# shoot1.net
KiCad netlist of a schematic drawn in Altium Designer
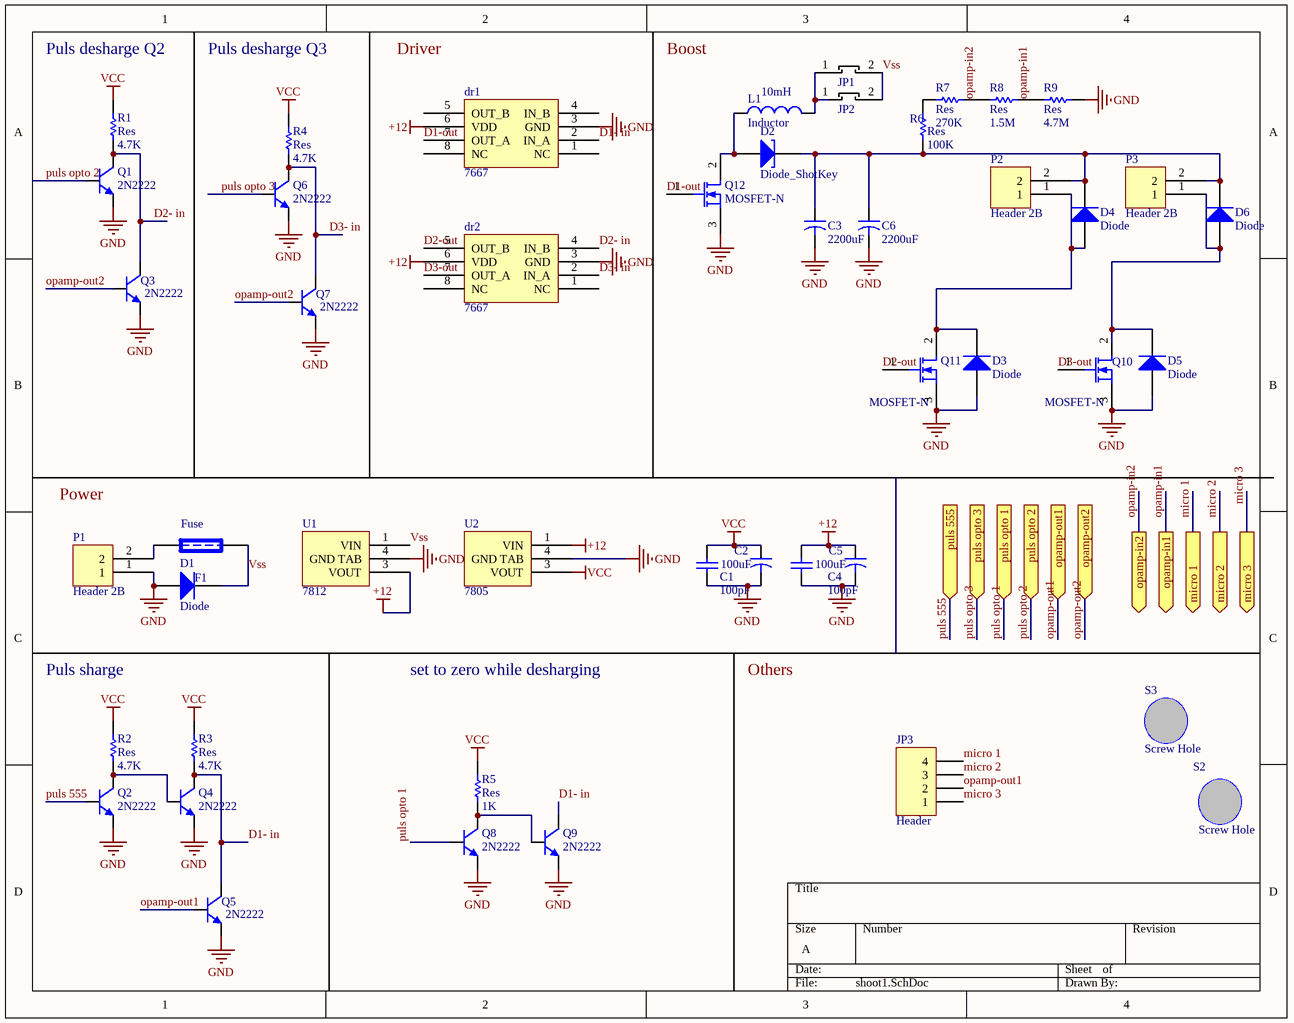
[diagram p0: shoot1.SchDoc]

(export (version "E")
  (design (tool "Eeschema 10.0.6"))
  (components
    (comp (ref "C1")
      (value "100pF")
      (footprint "2012[0805]")
      (description "Capacitor")
      (fields (field (name "Comment") "Cap_UP") (field (name "PUBLISHER") "Altium Limited"))
      (libsource (lib "KN2CLib") (part "Cap_UP"))
    )
    (comp (ref "C2")
      (value "100uF")
      (footprint "EL_M")
      (description "Capacitor")
      (fields (field (name "Comment") "Cap_El") (field (name "PUBLISHER") "Altium Limited"))
      (libsource (lib "KN2CLib") (part "Cap_El"))
    )
    (comp (ref "C3")
      (value "2200uF")
      (footprint "CAP")
      (description "Capacitor")
      (fields (field (name "Comment") "Cap_El_200V") (field (name "PUBLISHER") "Altium Limited"))
      (libsource (lib "KN2CLib") (part "Cap_El_200V"))
    )
    (comp (ref "C4")
      (value "100pF")
      (footprint "2012[0805]")
      (description "Capacitor")
      (fields (field (name "Comment") "Cap_UP") (field (name "PUBLISHER") "Altium Limited"))
      (libsource (lib "KN2CLib") (part "Cap_UP"))
    )
    (comp (ref "C5")
      (value "100uF")
      (footprint "EL_M")
      (description "Capacitor")
      (fields (field (name "Comment") "Cap_El") (field (name "PUBLISHER") "Altium Limited"))
      (libsource (lib "KN2CLib") (part "Cap_El"))
    )
    (comp (ref "C6")
      (value "2200uF")
      (footprint "CAP")
      (description "Capacitor")
      (fields (field (name "Comment") "Cap_El_200V") (field (name "PUBLISHER") "Altium Limited"))
      (libsource (lib "KN2CLib") (part "Cap_El_200V"))
    )
    (comp (ref "D1")
      (value "Diode")
      (footprint "US1M")
      (description "1 Amp General Purpose Rectifier")
      (fields (field (name "PUBLISHER") "Altium Limited"))
      (libsource (lib "KN2CLib") (part "Diode"))
    )
    (comp (ref "D2")
      (value "Diode_ShotKey")
      (footprint "TO-220A - duplicate")
      (description "1 Amp General Purpose Rectifier")
      (fields (field (name "PUBLISHER") "Altium Limited"))
      (libsource (lib "KN2CLib") (part "Diode_ShotKey"))
    )
    (comp (ref "D3")
      (value "Diode")
      (footprint "DIO10.46-5.3X2.8")
      (description "1 Amp General Purpose Rectifier")
      (fields (field (name "PUBLISHER") "Altium Limited"))
      (libsource (lib "KN2CLib") (part "Diode"))
    )
    (comp (ref "D4")
      (value "Diode")
      (footprint "DIO10.46-5.3X2.8")
      (description "1 Amp General Purpose Rectifier")
      (fields (field (name "PUBLISHER") "Altium Limited"))
      (libsource (lib "KN2CLib") (part "Diode"))
    )
    (comp (ref "D5")
      (value "Diode")
      (footprint "DIO10.46-5.3X2.8")
      (description "1 Amp General Purpose Rectifier")
      (fields (field (name "PUBLISHER") "Altium Limited"))
      (libsource (lib "KN2CLib") (part "Diode"))
    )
    (comp (ref "D6")
      (value "Diode")
      (footprint "DIO10.46-5.3X2.8")
      (description "1 Amp General Purpose Rectifier")
      (fields (field (name "PUBLISHER") "Altium Limited"))
      (libsource (lib "KN2CLib") (part "Diode"))
    )
    (comp (ref "dr1")
      (value "7667")
      (footprint "8 pin SOIC_M")
      (description "Dual MOSFET Driver")
      (libsource (lib "KN2CLib") (part "7667"))
    )
    (comp (ref "dr2")
      (value "7667")
      (footprint "8 pin SOIC_M")
      (description "Dual MOSFET Driver")
      (libsource (lib "KN2CLib") (part "7667"))
    )
    (comp (ref "F1")
      (value "Fuse")
      (footprint "fuse new")
      (fields (field (name "PUBLISHER") "Altium Limited"))
      (libsource (lib "KN2CLib") (part "Fuse"))
    )
    (comp (ref "JP1") (value "JUMPER") (footprint "JPR") (libsource (lib "KN2CLib") (part "JUMPER")))
    (comp (ref "JP2") (value "JUMPER") (footprint "JPR") (libsource (lib "KN2CLib") (part "JUMPER")))
    (comp (ref "JP3")
      (value "Header")
      (footprint "sucket-smd-4pin")
      (description "Header, 4-Pin")
      (fields (field (name "PUBLISHER") "Altium Limited"))
      (libsource (lib "KN2CLib") (part "Header 4"))
    )
    (comp (ref "L1")
      (value "Inductor")
      (footprint "mh2")
      (fields (field (name "ALTIUM_VALUE") "10mH") (field (name "PUBLISHER") "Altium Limited"))
      (libsource (lib "KN2CLib") (part "Inductor"))
    )
    (comp (ref "P1") (value "Header 2B") (footprint "BHDR1X2") (libsource (lib "KN2CLib") (part "Header 2B")))
    (comp (ref "P2") (value "Header 2B") (footprint "BHDR1X2") (libsource (lib "KN2CLib") (part "Header 2B")))
    (comp (ref "P3") (value "Header 2B") (footprint "BHDR1X2") (libsource (lib "KN2CLib") (part "Header 2B")))
    (comp (ref "Q1")
      (value "2N2222")
      (footprint "SOT-23")
      (description "NPN Bipolar Transistor")
      (fields (field (name "PUBLISHER") "Altium Limited"))
      (libsource (lib "KN2CLib") (part "2N2222"))
    )
    (comp (ref "Q2")
      (value "2N2222")
      (footprint "SOT-23")
      (description "NPN Bipolar Transistor")
      (fields (field (name "PUBLISHER") "Altium Limited"))
      (libsource (lib "KN2CLib") (part "2N2222"))
    )
    (comp (ref "Q3")
      (value "2N2222")
      (footprint "SOT-23")
      (description "NPN Bipolar Transistor")
      (fields (field (name "PUBLISHER") "Altium Limited"))
      (libsource (lib "KN2CLib") (part "2N2222"))
    )
    (comp (ref "Q4")
      (value "2N2222")
      (footprint "SOT-23")
      (description "NPN Bipolar Transistor")
      (fields (field (name "PUBLISHER") "Altium Limited"))
      (libsource (lib "KN2CLib") (part "2N2222"))
    )
    (comp (ref "Q5")
      (value "2N2222")
      (footprint "SOT-23")
      (description "NPN Bipolar Transistor")
      (fields (field (name "PUBLISHER") "Altium Limited"))
      (libsource (lib "KN2CLib") (part "2N2222"))
    )
    (comp (ref "Q6")
      (value "2N2222")
      (footprint "SOT-23")
      (description "NPN Bipolar Transistor")
      (fields (field (name "PUBLISHER") "Altium Limited"))
      (libsource (lib "KN2CLib") (part "2N2222"))
    )
    (comp (ref "Q7")
      (value "2N2222")
      (footprint "SOT-23")
      (description "NPN Bipolar Transistor")
      (fields (field (name "PUBLISHER") "Altium Limited"))
      (libsource (lib "KN2CLib") (part "2N2222"))
    )
    (comp (ref "Q8")
      (value "2N2222")
      (footprint "SOT-23")
      (description "NPN Bipolar Transistor")
      (fields (field (name "PUBLISHER") "Altium Limited"))
      (libsource (lib "KN2CLib") (part "2N2222"))
    )
    (comp (ref "Q9")
      (value "2N2222")
      (footprint "SOT-23")
      (description "NPN Bipolar Transistor")
      (fields (field (name "PUBLISHER") "Altium Limited"))
      (libsource (lib "KN2CLib") (part "2N2222"))
    )
    (comp (ref "Q10")
      (value "MOSFET-N")
      (footprint "TO247")
      (description "N-Channel MOSFET")
      (fields (field (name "PUBLISHER") "Altium Limited"))
      (libsource (lib "KN2CLib") (part "MOSFET-N"))
    )
    (comp (ref "Q11")
      (value "MOSFET-N")
      (footprint "TO247")
      (description "N-Channel MOSFET")
      (fields (field (name "PUBLISHER") "Altium Limited"))
      (libsource (lib "KN2CLib") (part "MOSFET-N"))
    )
    (comp (ref "Q12")
      (value "MOSFET-N")
      (footprint "TO247")
      (description "N-Channel MOSFET")
      (fields (field (name "PUBLISHER") "Altium Limited"))
      (libsource (lib "KN2CLib") (part "MOSFET-N"))
    )
    (comp (ref "R1")
      (value "Res")
      (footprint "2012[0805]")
      (description "Semiconductor Resistor")
      (fields (field (name "ALTIUM_VALUE") "4.7K") (field (name "PUBLISHER") "Altium Limited"))
      (libsource (lib "KN2CLib") (part "Res"))
    )
    (comp (ref "R2")
      (value "Res")
      (footprint "2012[0805]")
      (description "Semiconductor Resistor")
      (fields (field (name "ALTIUM_VALUE") "4.7K") (field (name "PUBLISHER") "Altium Limited"))
      (libsource (lib "KN2CLib") (part "Res"))
    )
    (comp (ref "R3")
      (value "Res")
      (footprint "2012[0805]")
      (description "Semiconductor Resistor")
      (fields (field (name "ALTIUM_VALUE") "4.7K") (field (name "PUBLISHER") "Altium Limited"))
      (libsource (lib "KN2CLib") (part "Res"))
    )
    (comp (ref "R4")
      (value "Res")
      (footprint "2012[0805]")
      (description "Semiconductor Resistor")
      (fields (field (name "ALTIUM_VALUE") "4.7K") (field (name "PUBLISHER") "Altium Limited"))
      (libsource (lib "KN2CLib") (part "Res"))
    )
    (comp (ref "R5")
      (value "Res")
      (footprint "2012[0805]")
      (description "Semiconductor Resistor")
      (fields (field (name "ALTIUM_VALUE") "1K") (field (name "PUBLISHER") "Altium Limited"))
      (libsource (lib "KN2CLib") (part "Res"))
    )
    (comp (ref "R6")
      (value "Res")
      (footprint "2012[0805]")
      (description "Semiconductor Resistor")
      (fields (field (name "ALTIUM_VALUE") "100K") (field (name "PUBLISHER") "Altium Limited"))
      (libsource (lib "KN2CLib") (part "Res"))
    )
    (comp (ref "R7")
      (value "Res")
      (footprint "2012[0805]")
      (description "Semiconductor Resistor")
      (fields (field (name "ALTIUM_VALUE") "270K") (field (name "PUBLISHER") "Altium Limited"))
      (libsource (lib "KN2CLib") (part "Res"))
    )
    (comp (ref "R8")
      (value "Res")
      (footprint "2012[0805]")
      (description "Semiconductor Resistor")
      (fields (field (name "ALTIUM_VALUE") "1.5M") (field (name "PUBLISHER") "Altium Limited"))
      (libsource (lib "KN2CLib") (part "Res"))
    )
    (comp (ref "R9")
      (value "Res")
      (footprint "2012[0805]")
      (description "Semiconductor Resistor")
      (fields (field (name "ALTIUM_VALUE") "4.7M") (field (name "PUBLISHER") "Altium Limited"))
      (libsource (lib "KN2CLib") (part "Res"))
    )
    (comp (ref "S2")
      (value "Screw Hole")
      (footprint "Screw Holw 3-6 mm")
      (libsource (lib "KN2CLib") (part "Screw Hole"))
    )
    (comp (ref "S3")
      (value "Screw Hole")
      (footprint "Screw Holw 3-6 mm")
      (libsource (lib "KN2CLib") (part "Screw Hole"))
    )
    (comp (ref "U1") (value "7812") (footprint "D-PACK") (libsource (lib "KN2CLib") (part "7812")))
    (comp (ref "U2") (value "7805") (footprint "D-PACK") (libsource (lib "KN2CLib") (part "7805")))
  )
  (nets
    (net (code "1") (name "+12") (class "Default")
      (node (ref "C4") (pin "2") (pinfunction "2_2") (pintype "passive"))
      (node (ref "C5") (pin "1") (pinfunction "1_1") (pintype "passive"))
      (node (ref "U1") (pin "3") (pinfunction "VOUT_3") (pintype "passive"))
      (node (ref "U2") (pin "1") (pinfunction "VIN_1") (pintype "passive"))
      (node (ref "dr1") (pin "6") (pinfunction "VDD_6") (pintype "passive"))
      (node (ref "dr2") (pin "6") (pinfunction "VDD_6") (pintype "passive"))
    )
    (net (code "3") (name "/D1- in") (class "Default")
      (node (ref "Q4") (pin "1") (pinfunction "C_1") (pintype "passive"))
      (node (ref "Q5") (pin "1") (pinfunction "C_1") (pintype "passive"))
      (node (ref "Q9") (pin "1") (pinfunction "C_1") (pintype "passive"))
      (node (ref "R3") (pin "1") (pinfunction "1_1") (pintype "passive"))
      (node (ref "dr1") (pin "2") (pinfunction "IN_A_2") (pintype "passive"))
    )
    (net (code "4") (name "/D1-out") (class "Default")
      (node (ref "Q12") (pin "1") (pinfunction "G_1") (pintype "passive"))
      (node (ref "dr1") (pin "7") (pinfunction "OUT_A_7") (pintype "passive"))
    )
    (net (code "5") (name "/D2- in") (class "Default")
      (node (ref "Q1") (pin "1") (pinfunction "C_1") (pintype "passive"))
      (node (ref "Q3") (pin "1") (pinfunction "C_1") (pintype "passive"))
      (node (ref "R1") (pin "1") (pinfunction "1_1") (pintype "passive"))
      (node (ref "dr2") (pin "4") (pinfunction "IN_B_4") (pintype "passive"))
    )
    (net (code "6") (name "/D2-out") (class "Default")
      (node (ref "Q11") (pin "1") (pinfunction "G_1") (pintype "passive"))
      (node (ref "dr2") (pin "5") (pinfunction "OUT_B_5") (pintype "passive"))
    )
    (net (code "7") (name "/D3- in") (class "Default")
      (node (ref "Q6") (pin "1") (pinfunction "C_1") (pintype "passive"))
      (node (ref "Q7") (pin "1") (pinfunction "C_1") (pintype "passive"))
      (node (ref "R4") (pin "1") (pinfunction "1_1") (pintype "passive"))
      (node (ref "dr2") (pin "2") (pinfunction "IN_A_2") (pintype "passive"))
    )
    (net (code "8") (name "/D3-out") (class "Default")
      (node (ref "Q10") (pin "1") (pinfunction "G_1") (pintype "passive"))
      (node (ref "dr2") (pin "7") (pinfunction "OUT_A_7") (pintype "passive"))
    )
    (net (code "12") (name "/Vss") (class "Default")
      (node (ref "D1") (pin "2") (pinfunction "K_2") (pintype "passive"))
      (node (ref "F1") (pin "2") (pinfunction "2_2") (pintype "passive"))
      (node (ref "JP1") (pin "2") (pinfunction "2_2") (pintype "passive"))
      (node (ref "JP2") (pin "2") (pinfunction "2_2") (pintype "passive"))
      (node (ref "U1") (pin "1") (pinfunction "VIN_1") (pintype "passive"))
    )
    (net (code "13") (name "/micro 1") (class "Default")
      (node (ref "JP3") (pin "4") (pinfunction "4_4") (pintype "passive"))
    )
    (net (code "14") (name "/micro 2") (class "Default")
      (node (ref "JP3") (pin "3") (pinfunction "3_3") (pintype "passive"))
    )
    (net (code "15") (name "/micro 3") (class "Default")
      (node (ref "JP3") (pin "1") (pinfunction "1_1") (pintype "passive"))
    )
    (net (code "16") (name "/opamp-in1") (class "Default")
      (node (ref "R8") (pin "1") (pinfunction "1_1") (pintype "passive"))
      (node (ref "R9") (pin "2") (pinfunction "2_2") (pintype "passive"))
    )
    (net (code "17") (name "/opamp-in2") (class "Default")
      (node (ref "R7") (pin "1") (pinfunction "1_1") (pintype "passive"))
      (node (ref "R8") (pin "2") (pinfunction "2_2") (pintype "passive"))
    )
    (net (code "18") (name "/opamp-out1") (class "Default")
      (node (ref "JP3") (pin "2") (pinfunction "2_2") (pintype "passive"))
      (node (ref "Q5") (pin "2") (pinfunction "B_2") (pintype "passive"))
    )
    (net (code "19") (name "/opamp-out2") (class "Default")
      (node (ref "Q3") (pin "2") (pinfunction "B_2") (pintype "passive"))
      (node (ref "Q7") (pin "2") (pinfunction "B_2") (pintype "passive"))
    )
    (net (code "20") (name "/puls 555") (class "Default")
      (node (ref "Q2") (pin "2") (pinfunction "B_2") (pintype "passive"))
    )
    (net (code "21") (name "/puls opto 1") (class "Default")
      (node (ref "Q8") (pin "2") (pinfunction "B_2") (pintype "passive"))
    )
    (net (code "22") (name "/puls opto 2") (class "Default")
      (node (ref "Q1") (pin "2") (pinfunction "B_2") (pintype "passive"))
    )
    (net (code "23") (name "/puls opto 3") (class "Default")
      (node (ref "Q6") (pin "2") (pinfunction "B_2") (pintype "passive"))
    )
    (net (code "24") (name "GND") (class "Default")
      (node (ref "C1") (pin "1") (pinfunction "1_1") (pintype "passive"))
      (node (ref "C2") (pin "2") (pinfunction "2_2") (pintype "passive"))
      (node (ref "C3") (pin "2") (pinfunction "2_2") (pintype "passive"))
      (node (ref "C4") (pin "1") (pinfunction "1_1") (pintype "passive"))
      (node (ref "C5") (pin "2") (pinfunction "2_2") (pintype "passive"))
      (node (ref "C6") (pin "2") (pinfunction "2_2") (pintype "passive"))
      (node (ref "D1") (pin "1") (pinfunction "A_1") (pintype "passive"))
      (node (ref "D3") (pin "1") (pinfunction "A_1") (pintype "passive"))
      (node (ref "D5") (pin "1") (pinfunction "A_1") (pintype "passive"))
      (node (ref "P1") (pin "1") (pinfunction "1_1") (pintype "passive"))
      (node (ref "Q1") (pin "3") (pinfunction "E_3") (pintype "passive"))
      (node (ref "Q10") (pin "3") (pinfunction "S_3") (pintype "passive"))
      (node (ref "Q11") (pin "3") (pinfunction "S_3") (pintype "passive"))
      (node (ref "Q12") (pin "3") (pinfunction "S_3") (pintype "passive"))
      (node (ref "Q2") (pin "3") (pinfunction "E_3") (pintype "passive"))
      (node (ref "Q3") (pin "3") (pinfunction "E_3") (pintype "passive"))
      (node (ref "Q4") (pin "3") (pinfunction "E_3") (pintype "passive"))
      (node (ref "Q5") (pin "3") (pinfunction "E_3") (pintype "passive"))
      (node (ref "Q6") (pin "3") (pinfunction "E_3") (pintype "passive"))
      (node (ref "Q7") (pin "3") (pinfunction "E_3") (pintype "passive"))
      (node (ref "Q8") (pin "3") (pinfunction "E_3") (pintype "passive"))
      (node (ref "Q9") (pin "3") (pinfunction "E_3") (pintype "passive"))
      (node (ref "R9") (pin "1") (pinfunction "1_1") (pintype "passive"))
      (node (ref "U1") (pin "4") (pinfunction "GND_TAB_4") (pintype "passive"))
      (node (ref "U2") (pin "4") (pinfunction "GND_TAB_4") (pintype "passive"))
      (node (ref "dr1") (pin "3") (pinfunction "GND_3") (pintype "passive"))
      (node (ref "dr2") (pin "3") (pinfunction "GND_3") (pintype "passive"))
    )
    (net (code "25") (name "Net-(D2-A)") (class "Default")
      (node (ref "D2") (pin "2") (pinfunction "A_2") (pintype "passive"))
      (node (ref "L1") (pin "1") (pinfunction "1_1") (pintype "passive"))
      (node (ref "Q12") (pin "2") (pinfunction "D_2") (pintype "passive"))
    )
    (net (code "26") (name "Net-(D2-K)") (class "Default")
      (node (ref "C3") (pin "1") (pinfunction "1_1") (pintype "passive"))
      (node (ref "C6") (pin "1") (pinfunction "1_1") (pintype "passive"))
      (node (ref "D2") (pin "1") (pinfunction "K_1") (pintype "passive"))
      (node (ref "D4") (pin "2") (pinfunction "K_2") (pintype "passive"))
      (node (ref "D6") (pin "2") (pinfunction "K_2") (pintype "passive"))
      (node (ref "P2") (pin "2") (pinfunction "2_2") (pintype "passive"))
      (node (ref "P3") (pin "2") (pinfunction "2_2") (pintype "passive"))
      (node (ref "R6") (pin "1") (pinfunction "1_1") (pintype "passive"))
    )
    (net (code "27") (name "Net-(D3-K)") (class "Default")
      (node (ref "D3") (pin "2") (pinfunction "K_2") (pintype "passive"))
      (node (ref "D4") (pin "1") (pinfunction "A_1") (pintype "passive"))
      (node (ref "P2") (pin "1") (pinfunction "1_1") (pintype "passive"))
      (node (ref "Q11") (pin "2") (pinfunction "D_2") (pintype "passive"))
    )
    (net (code "28") (name "Net-(D5-K)") (class "Default")
      (node (ref "D5") (pin "2") (pinfunction "K_2") (pintype "passive"))
      (node (ref "D6") (pin "1") (pinfunction "A_1") (pintype "passive"))
      (node (ref "P3") (pin "1") (pinfunction "1_1") (pintype "passive"))
      (node (ref "Q10") (pin "2") (pinfunction "D_2") (pintype "passive"))
    )
    (net (code "29") (name "Net-(F1-Pad1)") (class "Default")
      (node (ref "F1") (pin "1") (pinfunction "1_1") (pintype "passive"))
      (node (ref "P1") (pin "2") (pinfunction "2_2") (pintype "passive"))
    )
    (net (code "30") (name "Net-(JP1-Pad1)") (class "Default")
      (node (ref "JP1") (pin "1") (pinfunction "1_1") (pintype "passive"))
      (node (ref "JP2") (pin "1") (pinfunction "1_1") (pintype "passive"))
      (node (ref "L1") (pin "2") (pinfunction "2_2") (pintype "passive"))
    )
    (net (code "31") (name "Net-(Q2-C)") (class "Default")
      (node (ref "Q2") (pin "1") (pinfunction "C_1") (pintype "passive"))
      (node (ref "Q4") (pin "2") (pinfunction "B_2") (pintype "passive"))
      (node (ref "R2") (pin "1") (pinfunction "1_1") (pintype "passive"))
    )
    (net (code "32") (name "Net-(Q8-C)") (class "Default")
      (node (ref "Q8") (pin "1") (pinfunction "C_1") (pintype "passive"))
      (node (ref "Q9") (pin "2") (pinfunction "B_2") (pintype "passive"))
      (node (ref "R5") (pin "1") (pinfunction "1_1") (pintype "passive"))
    )
    (net (code "33") (name "Net-(R6-Pad2)") (class "Default")
      (node (ref "R6") (pin "2") (pinfunction "2_2") (pintype "passive"))
      (node (ref "R7") (pin "2") (pinfunction "2_2") (pintype "passive"))
    )
    (net (code "34") (name "VCC") (class "Default")
      (node (ref "C1") (pin "2") (pinfunction "2_2") (pintype "passive"))
      (node (ref "C2") (pin "1") (pinfunction "1_1") (pintype "passive"))
      (node (ref "R1") (pin "2") (pinfunction "2_2") (pintype "passive"))
      (node (ref "R2") (pin "2") (pinfunction "2_2") (pintype "passive"))
      (node (ref "R3") (pin "2") (pinfunction "2_2") (pintype "passive"))
      (node (ref "R4") (pin "2") (pinfunction "2_2") (pintype "passive"))
      (node (ref "R5") (pin "2") (pinfunction "2_2") (pintype "passive"))
      (node (ref "U2") (pin "3") (pinfunction "VOUT_3") (pintype "passive"))
    )
    (net (code "35") (name "unconnected-(dr1-IN_B-Pad4)") (class "Default")
      (node (ref "dr1") (pin "4") (pinfunction "IN_B_4") (pintype "passive"))
    )
    (net (code "36") (name "unconnected-(dr1-NC-Pad1)") (class "Default")
      (node (ref "dr1") (pin "1") (pinfunction "NC_1") (pintype "passive"))
    )
    (net (code "37") (name "unconnected-(dr1-NC-Pad8)") (class "Default")
      (node (ref "dr1") (pin "8") (pinfunction "NC_8") (pintype "passive"))
    )
    (net (code "38") (name "unconnected-(dr1-OUT_B-Pad5)") (class "Default")
      (node (ref "dr1") (pin "5") (pinfunction "OUT_B_5") (pintype "passive"))
    )
    (net (code "39") (name "unconnected-(dr2-NC-Pad1)") (class "Default")
      (node (ref "dr2") (pin "1") (pinfunction "NC_1") (pintype "passive"))
    )
    (net (code "40") (name "unconnected-(dr2-NC-Pad8)") (class "Default")
      (node (ref "dr2") (pin "8") (pinfunction "NC_8") (pintype "passive"))
    )
  )
)
